# FPGA_Banks_47_48_HP_FMC.net
KiCad netlist of a schematic drawn in Altium Designer
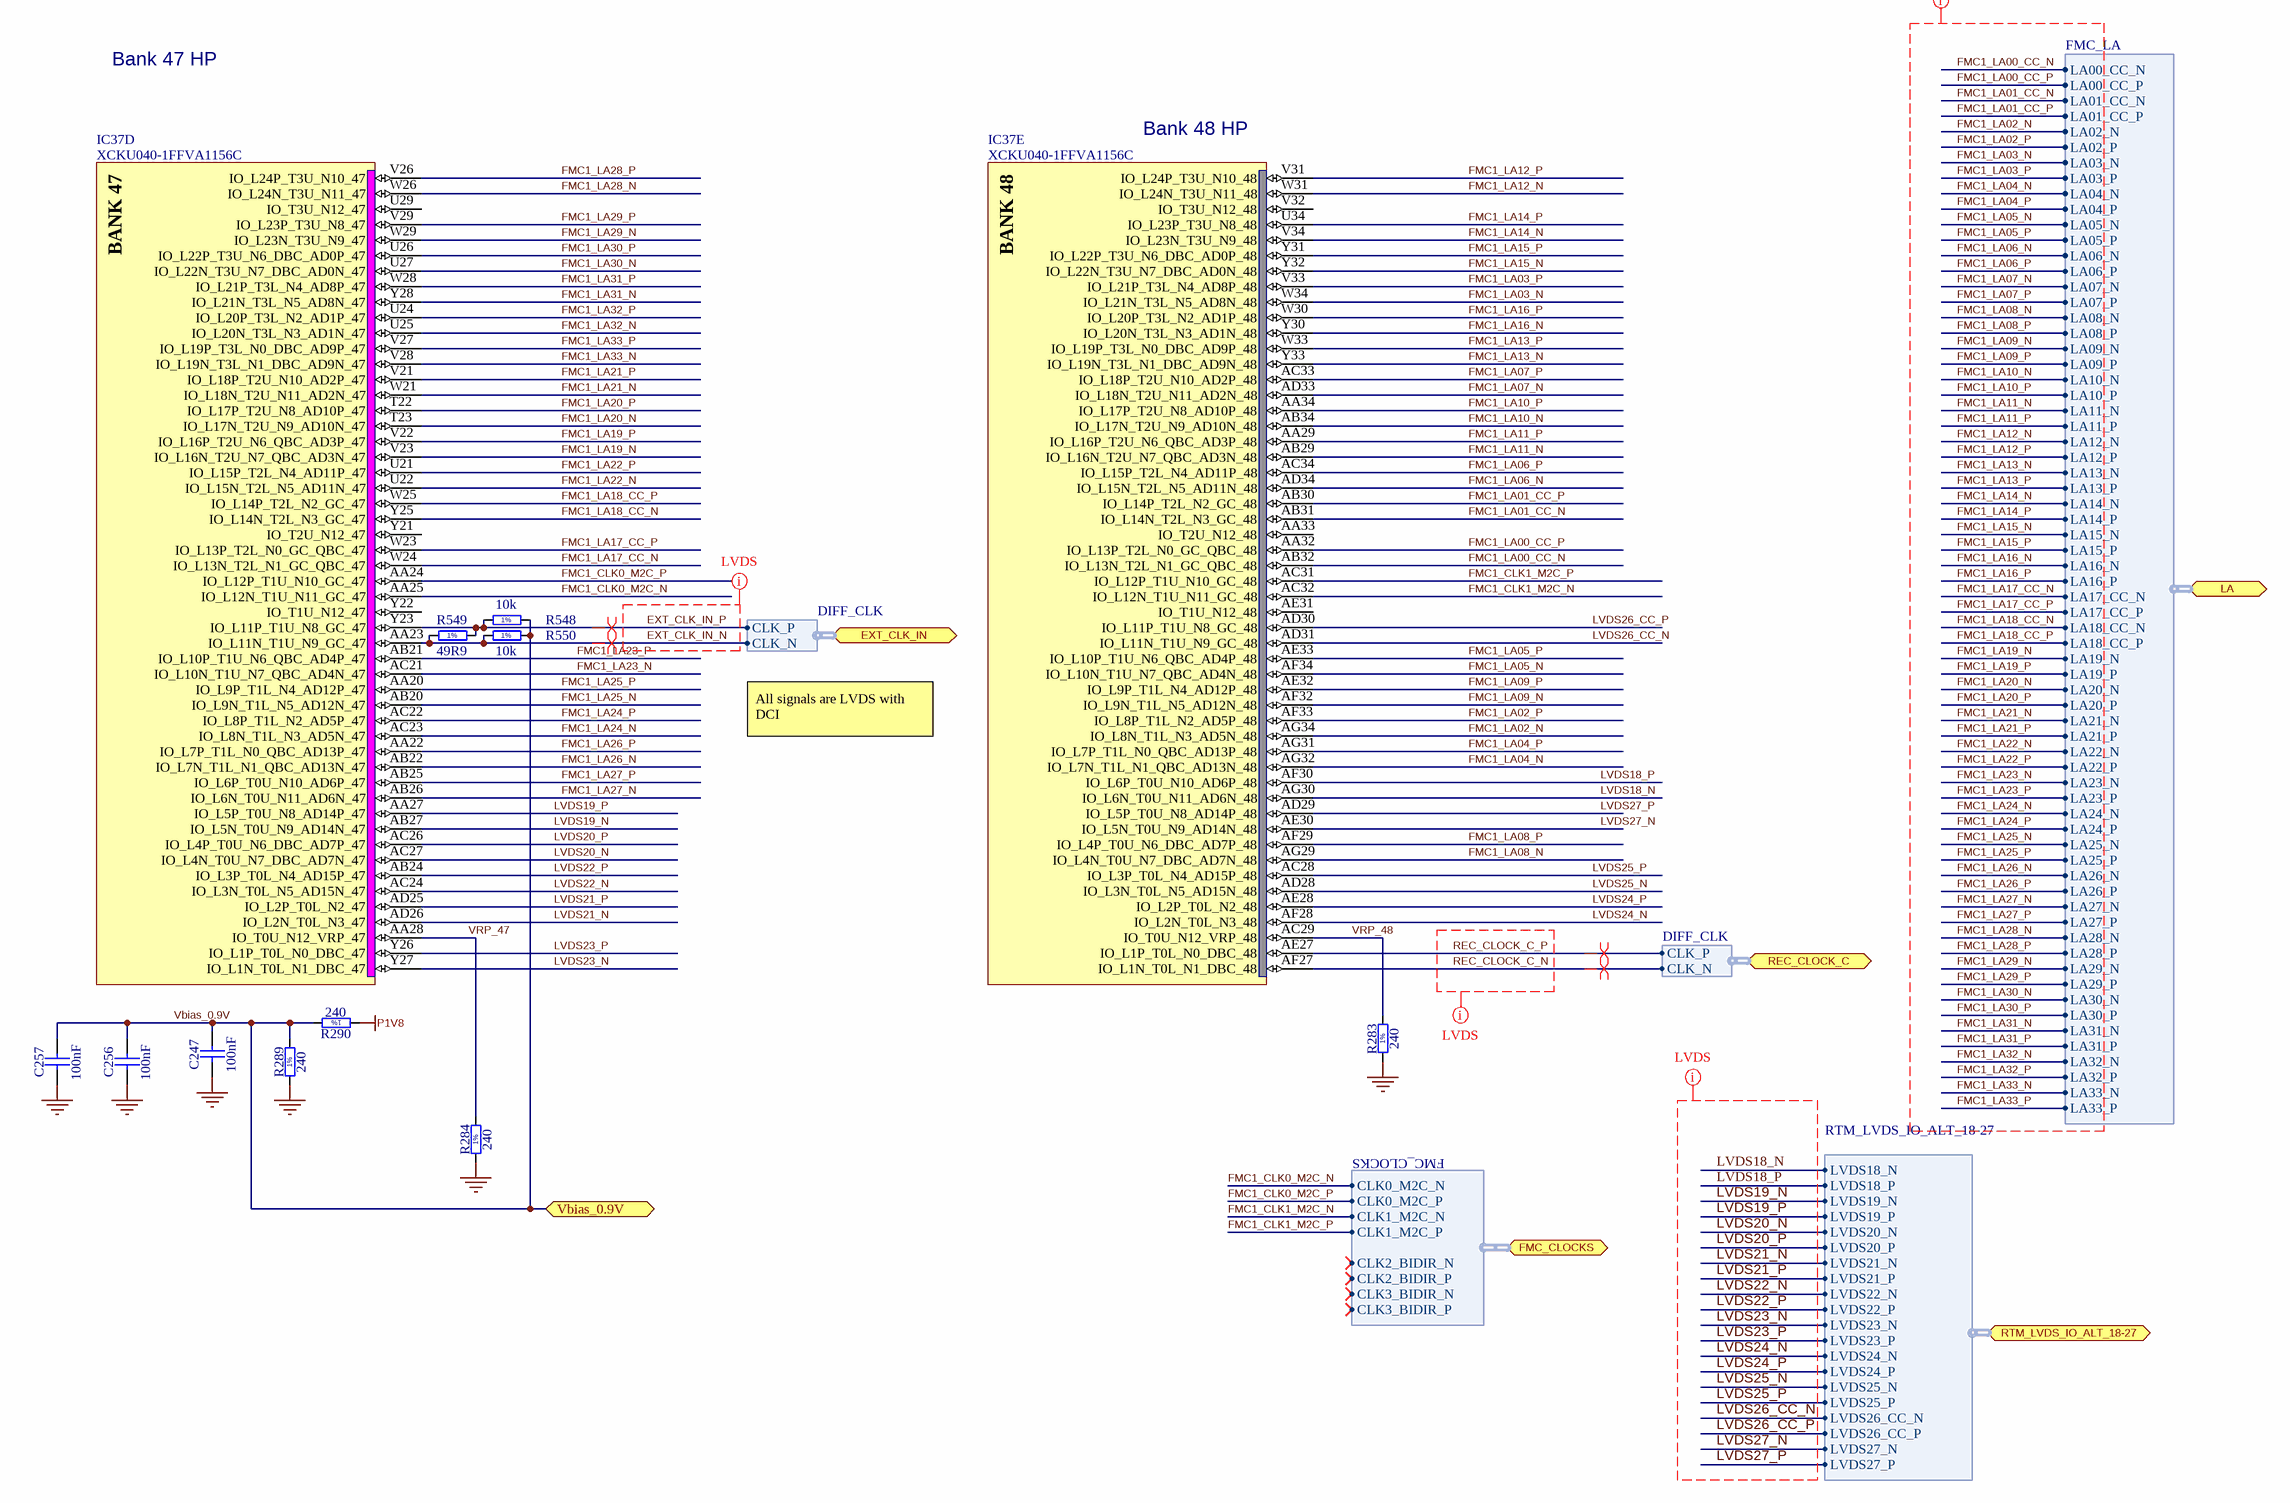
[diagram p0: FPGA_Banks_47_48_HP_FMC.SchDoc]

(export (version "E")
  (design (tool "Eeschema 10.0.6"))
  (components
    (comp (ref "C247")
      (value "100nF")
      (footprint "CAPC0603X33N")
      (description "Non-polarised capacitor")
      (fields
        (field (name "MANUFACTURER PART NUMBER") "CC0201_100NF_6.3V_10%_X5R")
        (field (name "MANUFACTURER") "GENERIC")
        (field (name "AUTHOR") "CERN DEM JLC")
      )
      (libsource (lib "Capacitors") (part "Capacitor - non polarized"))
    )
    (comp (ref "C256")
      (value "100nF")
      (footprint "CAPC0603X33N")
      (description "Non-polarised capacitor")
      (fields
        (field (name "MANUFACTURER PART NUMBER") "CC0201_100NF_6.3V_10%_X5R")
        (field (name "MANUFACTURER") "GENERIC")
        (field (name "AUTHOR") "CERN DEM JLC")
      )
      (libsource (lib "Capacitors") (part "Capacitor - non polarized"))
    )
    (comp (ref "C257")
      (value "100nF")
      (footprint "CAPC0603X33N")
      (description "Non-polarised capacitor")
      (fields
        (field (name "MANUFACTURER PART NUMBER") "CC0201_100NF_6.3V_10%_X5R")
        (field (name "MANUFACTURER") "GENERIC")
        (field (name "AUTHOR") "CERN DEM JLC")
      )
      (libsource (lib "Capacitors") (part "Capacitor - non polarized"))
    )
    (comp (ref "IC37")
      (value "XCKU040-1FFVA1156C")
      (footprint "BGA1156C100P34X34_3500X3500X350")
      (description "Kintex UltraScale FPGA, 520 I/O, 530K Cells, 1156-Ball BGA, Speed Grade 1, Commercial Grade")
      (fields (field (name "MANUFACTURER") "XILINX") (field (name "AUTHOR") "CERN DEM CA"))
      (libsource (lib "ICs And Semiconductors") (part "XCKU040-1FFVA1156C"))
    )
    (comp (ref "R283")
      (value "240")
      (footprint "RESC1005X40N")
      (description "Resistor - 1%")
      (fields
        (field (name "MANUFACTURER PART NUMBER") "R0402_240R_1%_0.0625W_100PPM")
        (field (name "MANUFACTURER") "GENERIC")
        (field (name "AUTHOR") "CERN DEM JLC")
      )
      (libsource (lib "Resistors") (part "Resistor - 1%"))
    )
    (comp (ref "R284")
      (value "240")
      (footprint "RESC1005X40N")
      (description "Resistor - 1%")
      (fields
        (field (name "MANUFACTURER PART NUMBER") "R0402_240R_1%_0.0625W_100PPM")
        (field (name "MANUFACTURER") "GENERIC")
        (field (name "AUTHOR") "CERN DEM JLC")
      )
      (libsource (lib "Resistors") (part "Resistor - 1%"))
    )
    (comp (ref "R289")
      (value "240")
      (footprint "RESC1005X40N")
      (description "Resistor - 1%")
      (fields
        (field (name "MANUFACTURER PART NUMBER") "R0402_240R_1%_0.0625W_100PPM")
        (field (name "MANUFACTURER") "GENERIC")
        (field (name "AUTHOR") "CERN DEM JLC")
      )
      (libsource (lib "Resistors") (part "Resistor - 1%"))
    )
    (comp (ref "R290")
      (value "240")
      (footprint "RESC1005X40N")
      (description "Resistor - 1%")
      (fields
        (field (name "MANUFACTURER PART NUMBER") "R0402_240R_1%_0.0625W_100PPM")
        (field (name "MANUFACTURER") "GENERIC")
        (field (name "AUTHOR") "CERN DEM JLC")
      )
      (libsource (lib "Resistors") (part "Resistor - 1%"))
    )
    (comp (ref "R548")
      (value "10k")
      (footprint "RESC1005X40N")
      (description "Resistor - 1%")
      (fields
        (field (name "MANUFACTURER PART NUMBER") "R0402_10K_1%_0.0625W_100PPM")
        (field (name "MANUFACTURER") "GENERIC")
        (field (name "AUTHOR") "CERN DEM JLC")
      )
      (libsource (lib "Resistors") (part "Resistor - 1%"))
    )
    (comp (ref "R549")
      (value "49R9")
      (footprint "RESC1005X40N")
      (description "Resistor - 1%")
      (fields
        (field (name "MANUFACTURER PART NUMBER") "R0402_49R9_1%_0.0625W_100PPM")
        (field (name "MANUFACTURER") "GENERIC")
        (field (name "AUTHOR") "CERN DEM JLC")
      )
      (libsource (lib "Resistors") (part "Resistor - 1%"))
    )
    (comp (ref "R550")
      (value "10k")
      (footprint "RESC1005X40N")
      (description "Resistor - 1%")
      (fields
        (field (name "MANUFACTURER PART NUMBER") "R0402_10K_1%_0.0625W_100PPM")
        (field (name "MANUFACTURER") "GENERIC")
        (field (name "AUTHOR") "CERN DEM JLC")
      )
      (libsource (lib "Resistors") (part "Resistor - 1%"))
    )
  )
  (nets
    (net (code "5") (name "/EXT_CLK_IN_N") (class "Default")
      (node (ref "IC37") (pin "AA23") (pinfunction "IO_L11N_T1U_N9_GC_47_AA23") (pintype "bidirectional"))
      (node (ref "R549") (pin "1") (pinfunction "1_1") (pintype "passive"))
      (node (ref "R550") (pin "1") (pinfunction "1_1") (pintype "passive"))
    )
    (net (code "6") (name "/EXT_CLK_IN_P") (class "Default")
      (node (ref "IC37") (pin "Y23") (pinfunction "IO_L11P_T1U_N8_GC_47_Y23") (pintype "bidirectional"))
      (node (ref "R548") (pin "1") (pinfunction "1_1") (pintype "passive"))
      (node (ref "R549") (pin "2") (pinfunction "2_2") (pintype "passive"))
    )
    (net (code "7") (name "/FMC1_CLK0_M2C_N") (class "Default")
      (node (ref "IC37") (pin "AA25") (pinfunction "IO_L12N_T1U_N11_GC_47_AA25") (pintype "bidirectional"))
    )
    (net (code "8") (name "/FMC1_CLK0_M2C_P") (class "Default")
      (node (ref "IC37") (pin "AA24") (pinfunction "IO_L12P_T1U_N10_GC_47_AA24") (pintype "bidirectional"))
    )
    (net (code "9") (name "/FMC1_CLK1_M2C_N") (class "Default")
      (node (ref "IC37") (pin "AC32") (pinfunction "IO_L12N_T1U_N11_GC_48_AC32") (pintype "bidirectional"))
    )
    (net (code "10") (name "/FMC1_CLK1_M2C_P") (class "Default")
      (node (ref "IC37") (pin "AC31") (pinfunction "IO_L12P_T1U_N10_GC_48_AC31") (pintype "bidirectional"))
    )
    (net (code "11") (name "/FMC1_LA00_CC_N") (class "Default")
      (node (ref "IC37") (pin "AB32") (pinfunction "IO_L13N_T2L_N1_GC_QBC_48_AB32") (pintype "bidirectional"))
    )
    (net (code "12") (name "/FMC1_LA00_CC_P") (class "Default")
      (node (ref "IC37") (pin "AA32") (pinfunction "IO_L13P_T2L_N0_GC_QBC_48_AA32") (pintype "bidirectional"))
    )
    (net (code "13") (name "/FMC1_LA01_CC_N") (class "Default")
      (node (ref "IC37") (pin "AB31") (pinfunction "IO_L14N_T2L_N3_GC_48_AB31") (pintype "bidirectional"))
    )
    (net (code "14") (name "/FMC1_LA01_CC_P") (class "Default")
      (node (ref "IC37") (pin "AB30") (pinfunction "IO_L14P_T2L_N2_GC_48_AB30") (pintype "bidirectional"))
    )
    (net (code "15") (name "/FMC1_LA02_N") (class "Default")
      (node (ref "IC37") (pin "AG34") (pinfunction "IO_L8N_T1L_N3_AD5N_48_AG34") (pintype "bidirectional"))
    )
    (net (code "16") (name "/FMC1_LA02_P") (class "Default")
      (node (ref "IC37") (pin "AF33") (pinfunction "IO_L8P_T1L_N2_AD5P_48_AF33") (pintype "bidirectional"))
    )
    (net (code "17") (name "/FMC1_LA03_N") (class "Default")
      (node (ref "IC37") (pin "W34") (pinfunction "IO_L21N_T3L_N5_AD8N_48_W34") (pintype "bidirectional"))
    )
    (net (code "18") (name "/FMC1_LA03_P") (class "Default")
      (node (ref "IC37") (pin "V33") (pinfunction "IO_L21P_T3L_N4_AD8P_48_V33") (pintype "bidirectional"))
    )
    (net (code "19") (name "/FMC1_LA04_N") (class "Default")
      (node (ref "IC37") (pin "AG32") (pinfunction "IO_L7N_T1L_N1_QBC_AD13N_48_AG32") (pintype "bidirectional"))
    )
    (net (code "20") (name "/FMC1_LA04_P") (class "Default")
      (node (ref "IC37") (pin "AG31") (pinfunction "IO_L7P_T1L_N0_QBC_AD13P_48_AG31") (pintype "bidirectional"))
    )
    (net (code "21") (name "/FMC1_LA05_N") (class "Default")
      (node (ref "IC37") (pin "AF34") (pinfunction "IO_L10N_T1U_N7_QBC_AD4N_48_AF34") (pintype "bidirectional"))
    )
    (net (code "22") (name "/FMC1_LA05_P") (class "Default")
      (node (ref "IC37") (pin "AE33") (pinfunction "IO_L10P_T1U_N6_QBC_AD4P_48_AE33") (pintype "bidirectional"))
    )
    (net (code "23") (name "/FMC1_LA06_N") (class "Default")
      (node (ref "IC37") (pin "AD34") (pinfunction "IO_L15N_T2L_N5_AD11N_48_AD34") (pintype "bidirectional"))
    )
    (net (code "24") (name "/FMC1_LA06_P") (class "Default")
      (node (ref "IC37") (pin "AC34") (pinfunction "IO_L15P_T2L_N4_AD11P_48_AC34") (pintype "bidirectional"))
    )
    (net (code "25") (name "/FMC1_LA07_N") (class "Default")
      (node (ref "IC37") (pin "AD33") (pinfunction "IO_L18N_T2U_N11_AD2N_48_AD33") (pintype "bidirectional"))
    )
    (net (code "26") (name "/FMC1_LA07_P") (class "Default")
      (node (ref "IC37") (pin "AC33") (pinfunction "IO_L18P_T2U_N10_AD2P_48_AC33") (pintype "bidirectional"))
    )
    (net (code "27") (name "/FMC1_LA08_N") (class "Default")
      (node (ref "IC37") (pin "AG29") (pinfunction "IO_L4N_T0U_N7_DBC_AD7N_48_AG29") (pintype "bidirectional"))
    )
    (net (code "28") (name "/FMC1_LA08_P") (class "Default")
      (node (ref "IC37") (pin "AF29") (pinfunction "IO_L4P_T0U_N6_DBC_AD7P_48_AF29") (pintype "bidirectional"))
    )
    (net (code "29") (name "/FMC1_LA09_N") (class "Default")
      (node (ref "IC37") (pin "AF32") (pinfunction "IO_L9N_T1L_N5_AD12N_48_AF32") (pintype "bidirectional"))
    )
    (net (code "30") (name "/FMC1_LA09_P") (class "Default")
      (node (ref "IC37") (pin "AE32") (pinfunction "IO_L9P_T1L_N4_AD12P_48_AE32") (pintype "bidirectional"))
    )
    (net (code "31") (name "/FMC1_LA10_N") (class "Default")
      (node (ref "IC37") (pin "AB34") (pinfunction "IO_L17N_T2U_N9_AD10N_48_AB34") (pintype "bidirectional"))
    )
    (net (code "32") (name "/FMC1_LA10_P") (class "Default")
      (node (ref "IC37") (pin "AA34") (pinfunction "IO_L17P_T2U_N8_AD10P_48_AA34") (pintype "bidirectional"))
    )
    (net (code "33") (name "/FMC1_LA11_N") (class "Default")
      (node (ref "IC37") (pin "AB29") (pinfunction "IO_L16N_T2U_N7_QBC_AD3N_48_AB29") (pintype "bidirectional"))
    )
    (net (code "34") (name "/FMC1_LA11_P") (class "Default")
      (node (ref "IC37") (pin "AA29") (pinfunction "IO_L16P_T2U_N6_QBC_AD3P_48_AA29") (pintype "bidirectional"))
    )
    (net (code "35") (name "/FMC1_LA12_N") (class "Default")
      (node (ref "IC37") (pin "W31") (pinfunction "IO_L24N_T3U_N11_48_W31") (pintype "bidirectional"))
    )
    (net (code "36") (name "/FMC1_LA12_P") (class "Default")
      (node (ref "IC37") (pin "V31") (pinfunction "IO_L24P_T3U_N10_48_V31") (pintype "bidirectional"))
    )
    (net (code "37") (name "/FMC1_LA13_N") (class "Default")
      (node (ref "IC37") (pin "Y33") (pinfunction "IO_L19N_T3L_N1_DBC_AD9N_48_Y33") (pintype "bidirectional"))
    )
    (net (code "38") (name "/FMC1_LA13_P") (class "Default")
      (node (ref "IC37") (pin "W33") (pinfunction "IO_L19P_T3L_N0_DBC_AD9P_48_W33") (pintype "bidirectional"))
    )
    (net (code "39") (name "/FMC1_LA14_N") (class "Default")
      (node (ref "IC37") (pin "V34") (pinfunction "IO_L23N_T3U_N9_48_V34") (pintype "bidirectional"))
    )
    (net (code "40") (name "/FMC1_LA14_P") (class "Default")
      (node (ref "IC37") (pin "U34") (pinfunction "IO_L23P_T3U_N8_48_U34") (pintype "bidirectional"))
    )
    (net (code "41") (name "/FMC1_LA15_N") (class "Default")
      (node (ref "IC37") (pin "Y32") (pinfunction "IO_L22N_T3U_N7_DBC_AD0N_48_Y32") (pintype "bidirectional"))
    )
    (net (code "42") (name "/FMC1_LA15_P") (class "Default")
      (node (ref "IC37") (pin "Y31") (pinfunction "IO_L22P_T3U_N6_DBC_AD0P_48_Y31") (pintype "bidirectional"))
    )
    (net (code "43") (name "/FMC1_LA16_N") (class "Default")
      (node (ref "IC37") (pin "Y30") (pinfunction "IO_L20N_T3L_N3_AD1N_48_Y30") (pintype "bidirectional"))
    )
    (net (code "44") (name "/FMC1_LA16_P") (class "Default")
      (node (ref "IC37") (pin "W30") (pinfunction "IO_L20P_T3L_N2_AD1P_48_W30") (pintype "bidirectional"))
    )
    (net (code "45") (name "/FMC1_LA17_CC_N") (class "Default")
      (node (ref "IC37") (pin "W24") (pinfunction "IO_L13N_T2L_N1_GC_QBC_47_W24") (pintype "bidirectional"))
    )
    (net (code "46") (name "/FMC1_LA17_CC_P") (class "Default")
      (node (ref "IC37") (pin "W23") (pinfunction "IO_L13P_T2L_N0_GC_QBC_47_W23") (pintype "bidirectional"))
    )
    (net (code "47") (name "/FMC1_LA18_CC_N") (class "Default")
      (node (ref "IC37") (pin "Y25") (pinfunction "IO_L14N_T2L_N3_GC_47_Y25") (pintype "bidirectional"))
    )
    (net (code "48") (name "/FMC1_LA18_CC_P") (class "Default")
      (node (ref "IC37") (pin "W25") (pinfunction "IO_L14P_T2L_N2_GC_47_W25") (pintype "bidirectional"))
    )
    (net (code "49") (name "/FMC1_LA19_N") (class "Default")
      (node (ref "IC37") (pin "V23") (pinfunction "IO_L16N_T2U_N7_QBC_AD3N_47_V23") (pintype "bidirectional"))
    )
    (net (code "50") (name "/FMC1_LA19_P") (class "Default")
      (node (ref "IC37") (pin "V22") (pinfunction "IO_L16P_T2U_N6_QBC_AD3P_47_V22") (pintype "bidirectional"))
    )
    (net (code "51") (name "/FMC1_LA20_N") (class "Default")
      (node (ref "IC37") (pin "T23") (pinfunction "IO_L17N_T2U_N9_AD10N_47_T23") (pintype "bidirectional"))
    )
    (net (code "52") (name "/FMC1_LA20_P") (class "Default")
      (node (ref "IC37") (pin "T22") (pinfunction "IO_L17P_T2U_N8_AD10P_47_T22") (pintype "bidirectional"))
    )
    (net (code "53") (name "/FMC1_LA21_N") (class "Default")
      (node (ref "IC37") (pin "W21") (pinfunction "IO_L18N_T2U_N11_AD2N_47_W21") (pintype "bidirectional"))
    )
    (net (code "54") (name "/FMC1_LA21_P") (class "Default")
      (node (ref "IC37") (pin "V21") (pinfunction "IO_L18P_T2U_N10_AD2P_47_V21") (pintype "bidirectional"))
    )
    (net (code "55") (name "/FMC1_LA22_N") (class "Default")
      (node (ref "IC37") (pin "U22") (pinfunction "IO_L15N_T2L_N5_AD11N_47_U22") (pintype "bidirectional"))
    )
    (net (code "56") (name "/FMC1_LA22_P") (class "Default")
      (node (ref "IC37") (pin "U21") (pinfunction "IO_L15P_T2L_N4_AD11P_47_U21") (pintype "bidirectional"))
    )
    (net (code "57") (name "/FMC1_LA23_N") (class "Default")
      (node (ref "IC37") (pin "AC21") (pinfunction "IO_L10N_T1U_N7_QBC_AD4N_47_AC21") (pintype "bidirectional"))
    )
    (net (code "58") (name "/FMC1_LA23_P") (class "Default")
      (node (ref "IC37") (pin "AB21") (pinfunction "IO_L10P_T1U_N6_QBC_AD4P_47_AB21") (pintype "bidirectional"))
    )
    (net (code "59") (name "/FMC1_LA24_N") (class "Default")
      (node (ref "IC37") (pin "AC23") (pinfunction "IO_L8N_T1L_N3_AD5N_47_AC23") (pintype "bidirectional"))
    )
    (net (code "60") (name "/FMC1_LA24_P") (class "Default")
      (node (ref "IC37") (pin "AC22") (pinfunction "IO_L8P_T1L_N2_AD5P_47_AC22") (pintype "bidirectional"))
    )
    (net (code "61") (name "/FMC1_LA25_N") (class "Default")
      (node (ref "IC37") (pin "AB20") (pinfunction "IO_L9N_T1L_N5_AD12N_47_AB20") (pintype "bidirectional"))
    )
    (net (code "62") (name "/FMC1_LA25_P") (class "Default")
      (node (ref "IC37") (pin "AA20") (pinfunction "IO_L9P_T1L_N4_AD12P_47_AA20") (pintype "bidirectional"))
    )
    (net (code "63") (name "/FMC1_LA26_N") (class "Default")
      (node (ref "IC37") (pin "AB22") (pinfunction "IO_L7N_T1L_N1_QBC_AD13N_47_AB22") (pintype "bidirectional"))
    )
    (net (code "64") (name "/FMC1_LA26_P") (class "Default")
      (node (ref "IC37") (pin "AA22") (pinfunction "IO_L7P_T1L_N0_QBC_AD13P_47_AA22") (pintype "bidirectional"))
    )
    (net (code "65") (name "/FMC1_LA27_N") (class "Default")
      (node (ref "IC37") (pin "AB26") (pinfunction "IO_L6N_T0U_N11_AD6N_47_AB26") (pintype "bidirectional"))
    )
    (net (code "66") (name "/FMC1_LA27_P") (class "Default")
      (node (ref "IC37") (pin "AB25") (pinfunction "IO_L6P_T0U_N10_AD6P_47_AB25") (pintype "bidirectional"))
    )
    (net (code "67") (name "/FMC1_LA28_N") (class "Default")
      (node (ref "IC37") (pin "W26") (pinfunction "IO_L24N_T3U_N11_47_W26") (pintype "bidirectional"))
    )
    (net (code "68") (name "/FMC1_LA28_P") (class "Default")
      (node (ref "IC37") (pin "V26") (pinfunction "IO_L24P_T3U_N10_47_V26") (pintype "bidirectional"))
    )
    (net (code "69") (name "/FMC1_LA29_N") (class "Default")
      (node (ref "IC37") (pin "W29") (pinfunction "IO_L23N_T3U_N9_47_W29") (pintype "bidirectional"))
    )
    (net (code "70") (name "/FMC1_LA29_P") (class "Default")
      (node (ref "IC37") (pin "V29") (pinfunction "IO_L23P_T3U_N8_47_V29") (pintype "bidirectional"))
    )
    (net (code "71") (name "/FMC1_LA30_N") (class "Default")
      (node (ref "IC37") (pin "U27") (pinfunction "IO_L22N_T3U_N7_DBC_AD0N_47_U27") (pintype "bidirectional"))
    )
    (net (code "72") (name "/FMC1_LA30_P") (class "Default")
      (node (ref "IC37") (pin "U26") (pinfunction "IO_L22P_T3U_N6_DBC_AD0P_47_U26") (pintype "bidirectional"))
    )
    (net (code "73") (name "/FMC1_LA31_N") (class "Default")
      (node (ref "IC37") (pin "Y28") (pinfunction "IO_L21N_T3L_N5_AD8N_47_Y28") (pintype "bidirectional"))
    )
    (net (code "74") (name "/FMC1_LA31_P") (class "Default")
      (node (ref "IC37") (pin "W28") (pinfunction "IO_L21P_T3L_N4_AD8P_47_W28") (pintype "bidirectional"))
    )
    (net (code "75") (name "/FMC1_LA32_N") (class "Default")
      (node (ref "IC37") (pin "U25") (pinfunction "IO_L20N_T3L_N3_AD1N_47_U25") (pintype "bidirectional"))
    )
    (net (code "76") (name "/FMC1_LA32_P") (class "Default")
      (node (ref "IC37") (pin "U24") (pinfunction "IO_L20P_T3L_N2_AD1P_47_U24") (pintype "bidirectional"))
    )
    (net (code "77") (name "/FMC1_LA33_N") (class "Default")
      (node (ref "IC37") (pin "V28") (pinfunction "IO_L19N_T3L_N1_DBC_AD9N_47_V28") (pintype "bidirectional"))
    )
    (net (code "78") (name "/FMC1_LA33_P") (class "Default")
      (node (ref "IC37") (pin "V27") (pinfunction "IO_L19P_T3L_N0_DBC_AD9P_47_V27") (pintype "bidirectional"))
    )
    (net (code "79") (name "/LVDS18_N") (class "Default")
      (node (ref "IC37") (pin "AG30") (pinfunction "IO_L6N_T0U_N11_AD6N_48_AG30") (pintype "bidirectional"))
    )
    (net (code "80") (name "/LVDS18_P") (class "Default")
      (node (ref "IC37") (pin "AF30") (pinfunction "IO_L6P_T0U_N10_AD6P_48_AF30") (pintype "bidirectional"))
    )
    (net (code "81") (name "/LVDS19_N") (class "Default")
      (node (ref "IC37") (pin "AB27") (pinfunction "IO_L5N_T0U_N9_AD14N_47_AB27") (pintype "bidirectional"))
    )
    (net (code "82") (name "/LVDS19_P") (class "Default")
      (node (ref "IC37") (pin "AA27") (pinfunction "IO_L5P_T0U_N8_AD14P_47_AA27") (pintype "bidirectional"))
    )
    (net (code "83") (name "/LVDS20_N") (class "Default")
      (node (ref "IC37") (pin "AC27") (pinfunction "IO_L4N_T0U_N7_DBC_AD7N_47_AC27") (pintype "bidirectional"))
    )
    (net (code "84") (name "/LVDS20_P") (class "Default")
      (node (ref "IC37") (pin "AC26") (pinfunction "IO_L4P_T0U_N6_DBC_AD7P_47_AC26") (pintype "bidirectional"))
    )
    (net (code "85") (name "/LVDS21_N") (class "Default")
      (node (ref "IC37") (pin "AD26") (pinfunction "IO_L2N_T0L_N3_47_AD26") (pintype "bidirectional"))
    )
    (net (code "86") (name "/LVDS21_P") (class "Default")
      (node (ref "IC37") (pin "AD25") (pinfunction "IO_L2P_T0L_N2_47_AD25") (pintype "bidirectional"))
    )
    (net (code "87") (name "/LVDS22_N") (class "Default")
      (node (ref "IC37") (pin "AC24") (pinfunction "IO_L3N_T0L_N5_AD15N_47_AC24") (pintype "bidirectional"))
    )
    (net (code "88") (name "/LVDS22_P") (class "Default")
      (node (ref "IC37") (pin "AB24") (pinfunction "IO_L3P_T0L_N4_AD15P_47_AB24") (pintype "bidirectional"))
    )
    (net (code "89") (name "/LVDS23_N") (class "Default")
      (node (ref "IC37") (pin "Y27") (pinfunction "IO_L1N_T0L_N1_DBC_47_Y27") (pintype "bidirectional"))
    )
    (net (code "90") (name "/LVDS23_P") (class "Default")
      (node (ref "IC37") (pin "Y26") (pinfunction "IO_L1P_T0L_N0_DBC_47_Y26") (pintype "bidirectional"))
    )
    (net (code "91") (name "/LVDS24_N") (class "Default")
      (node (ref "IC37") (pin "AF28") (pinfunction "IO_L2N_T0L_N3_48_AF28") (pintype "bidirectional"))
    )
    (net (code "92") (name "/LVDS24_P") (class "Default")
      (node (ref "IC37") (pin "AE28") (pinfunction "IO_L2P_T0L_N2_48_AE28") (pintype "bidirectional"))
    )
    (net (code "93") (name "/LVDS25_N") (class "Default")
      (node (ref "IC37") (pin "AD28") (pinfunction "IO_L3N_T0L_N5_AD15N_48_AD28") (pintype "bidirectional"))
    )
    (net (code "94") (name "/LVDS25_P") (class "Default")
      (node (ref "IC37") (pin "AC28") (pinfunction "IO_L3P_T0L_N4_AD15P_48_AC28") (pintype "bidirectional"))
    )
    (net (code "95") (name "/LVDS26_CC_N") (class "Default")
      (node (ref "IC37") (pin "AD31") (pinfunction "IO_L11N_T1U_N9_GC_48_AD31") (pintype "bidirectional"))
    )
    (net (code "96") (name "/LVDS26_CC_P") (class "Default")
      (node (ref "IC37") (pin "AD30") (pinfunction "IO_L11P_T1U_N8_GC_48_AD30") (pintype "bidirectional"))
    )
    (net (code "97") (name "/LVDS27_N") (class "Default")
      (node (ref "IC37") (pin "AE30") (pinfunction "IO_L5N_T0U_N9_AD14N_48_AE30") (pintype "bidirectional"))
    )
    (net (code "98") (name "/LVDS27_P") (class "Default")
      (node (ref "IC37") (pin "AD29") (pinfunction "IO_L5P_T0U_N8_AD14P_48_AD29") (pintype "bidirectional"))
    )
    (net (code "99") (name "/REC_CLOCK_C_N") (class "Default")
      (node (ref "IC37") (pin "AF27") (pinfunction "IO_L1N_T0L_N1_DBC_48_AF27") (pintype "bidirectional"))
    )
    (net (code "100") (name "/REC_CLOCK_C_P") (class "Default")
      (node (ref "IC37") (pin "AE27") (pinfunction "IO_L1P_T0L_N0_DBC_48_AE27") (pintype "bidirectional"))
    )
    (net (code "101") (name "/VRP_47") (class "Default")
      (node (ref "IC37") (pin "AA28") (pinfunction "IO_T0U_N12_VRP_47_AA28") (pintype "bidirectional"))
      (node (ref "R284") (pin "2") (pinfunction "2_2") (pintype "passive"))
    )
    (net (code "102") (name "/VRP_48") (class "Default")
      (node (ref "IC37") (pin "AC29") (pinfunction "IO_T0U_N12_VRP_48_AC29") (pintype "bidirectional"))
      (node (ref "R283") (pin "2") (pinfunction "2_2") (pintype "passive"))
    )
    (net (code "103") (name "/Vbias_0.9V") (class "Default")
      (node (ref "C247") (pin "1") (pinfunction "1_1") (pintype "passive"))
      (node (ref "C256") (pin "1") (pinfunction "1_1") (pintype "passive"))
      (node (ref "C257") (pin "1") (pinfunction "1_1") (pintype "passive"))
      (node (ref "R289") (pin "2") (pinfunction "2_2") (pintype "passive"))
      (node (ref "R290") (pin "2") (pinfunction "2_2") (pintype "passive"))
      (node (ref "R548") (pin "2") (pinfunction "2_2") (pintype "passive"))
      (node (ref "R550") (pin "2") (pinfunction "2_2") (pintype "passive"))
    )
    (net (code "108") (name "GND") (class "Default")
      (node (ref "C247") (pin "2") (pinfunction "2_2") (pintype "passive"))
      (node (ref "C256") (pin "2") (pinfunction "2_2") (pintype "passive"))
      (node (ref "C257") (pin "2") (pinfunction "2_2") (pintype "passive"))
      (node (ref "R283") (pin "1") (pinfunction "1_1") (pintype "passive"))
      (node (ref "R284") (pin "1") (pinfunction "1_1") (pintype "passive"))
      (node (ref "R289") (pin "1") (pinfunction "1_1") (pintype "passive"))
    )
    (net (code "109") (name "P1V8") (class "Default")
      (node (ref "R290") (pin "1") (pinfunction "1_1") (pintype "passive"))
    )
    (net (code "110") (name "unconnected-(IC37D-IO_T1U_N12_47-PadY22)") (class "Default")
      (node (ref "IC37") (pin "Y22") (pinfunction "IO_T1U_N12_47_Y22") (pintype "bidirectional"))
    )
    (net (code "111") (name "unconnected-(IC37D-IO_T2U_N12_47-PadY21)") (class "Default")
      (node (ref "IC37") (pin "Y21") (pinfunction "IO_T2U_N12_47_Y21") (pintype "bidirectional"))
    )
    (net (code "112") (name "unconnected-(IC37D-IO_T3U_N12_47-PadU29)") (class "Default")
      (node (ref "IC37") (pin "U29") (pinfunction "IO_T3U_N12_47_U29") (pintype "bidirectional"))
    )
    (net (code "113") (name "unconnected-(IC37E-IO_T1U_N12_48-PadAE31)") (class "Default")
      (node (ref "IC37") (pin "AE31") (pinfunction "IO_T1U_N12_48_AE31") (pintype "bidirectional"))
    )
    (net (code "114") (name "unconnected-(IC37E-IO_T2U_N12_48-PadAA33)") (class "Default")
      (node (ref "IC37") (pin "AA33") (pinfunction "IO_T2U_N12_48_AA33") (pintype "bidirectional"))
    )
    (net (code "115") (name "unconnected-(IC37E-IO_T3U_N12_48-PadV32)") (class "Default")
      (node (ref "IC37") (pin "V32") (pinfunction "IO_T3U_N12_48_V32") (pintype "bidirectional"))
    )
  )
)
